# LeTalk.net
KiCad netlist of a schematic drawn in EasyEDA Pro
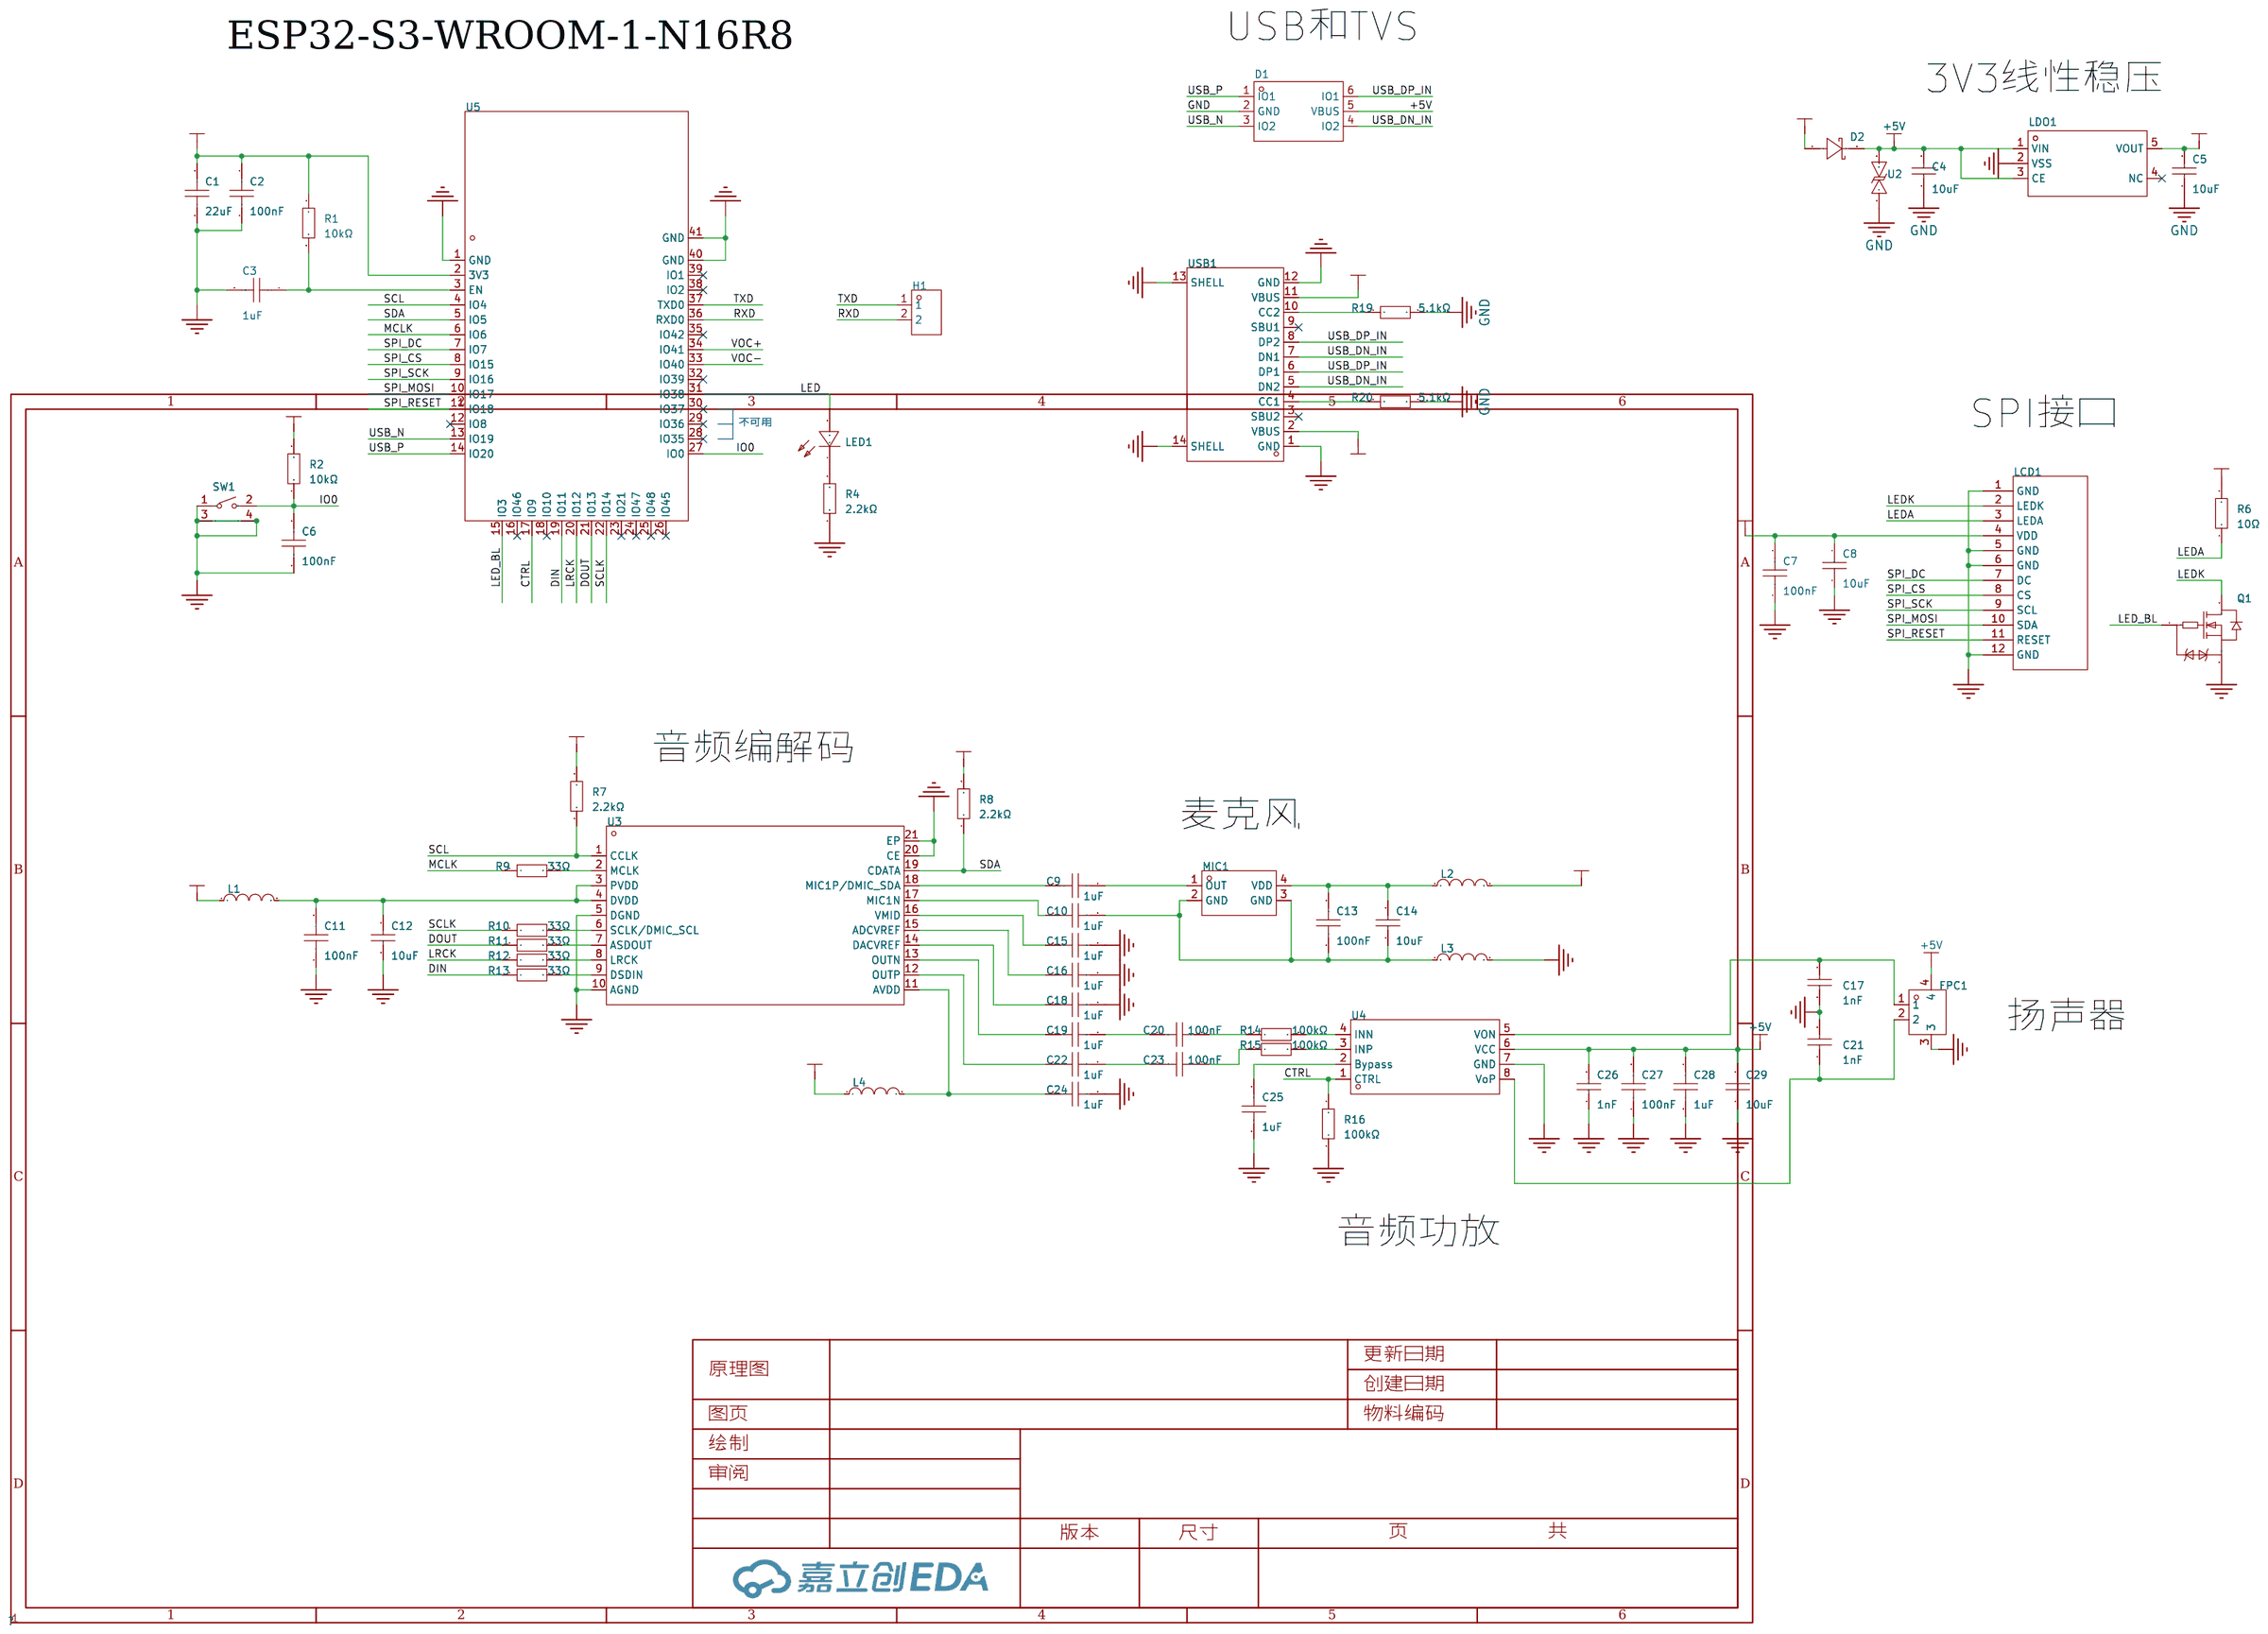
[diagram p0: schematic sheet]

(export (version "E")
  (design (tool "Eeschema 10.0.6"))
  (components
    (comp (ref "C1")
      (value "22uF")
      (footprint "easyedapro:C0603")
      (description "温度系数:X5R;精度:±20%;额定电压:10V;容值:22uF;")
      (fields
        (field (name "Manufacturer Part") "CL10A226MP8NUNE")
        (field (name "Manufacturer") "SAMSUNG(三星)")
      )
      (libsource (lib "easyedapro") (part "CL10A226MP8NUNE"))
    )
    (comp (ref "C2")
      (value "100nF")
      (footprint "easyedapro:C0402")
      (description "容值:100nF;精度:±10%;额定电压:16V;材质(温度系数):X7R;")
      (fields
        (field (name "Manufacturer Part") "CC0402KRX7R7BB104")
        (field (name "Manufacturer") "YAGEO(国巨)")
      )
      (libsource (lib "easyedapro") (part "CC0402KRX7R7BB104"))
    )
    (comp (ref "C3")
      (value "1uF")
      (footprint "easyedapro:C0402")
      (description "容值:1uF;精度:±10%;额定电压:25V;材质(温度系数):X5R;")
      (fields
        (field (name "Manufacturer Part") "CL05A105KA5NQNC")
        (field (name "Manufacturer") "SAMSUNG(三星)")
      )
      (libsource (lib "easyedapro") (part "CL05A105KA5NQNC"))
    )
    (comp (ref "C4")
      (value "10uF")
      (footprint "easyedapro:C0402")
      (description "容值:10uF;精度:±20%;额定电压:6.3V;材质(温度系数):X5R;")
      (fields
        (field (name "Manufacturer Part") "CL05A106MQ5NUNC")
        (field (name "Manufacturer") "SAMSUNG(三星)")
      )
      (libsource (lib "easyedapro") (part "CL05A106MQ5NUNC"))
    )
    (comp (ref "C5")
      (value "10uF")
      (footprint "easyedapro:C0402")
      (description "容值:10uF;精度:±20%;额定电压:6.3V;材质(温度系数):X5R;")
      (fields
        (field (name "Manufacturer Part") "CL05A106MQ5NUNC")
        (field (name "Manufacturer") "SAMSUNG(三星)")
      )
      (libsource (lib "easyedapro") (part "CL05A106MQ5NUNC"))
    )
    (comp (ref "C6")
      (value "100nF")
      (footprint "easyedapro:C0402")
      (description "容值:100nF;精度:±10%;额定电压:16V;材质(温度系数):X7R;")
      (fields
        (field (name "Manufacturer Part") "CC0402KRX7R7BB104")
        (field (name "Manufacturer") "YAGEO(国巨)")
      )
      (libsource (lib "easyedapro") (part "CC0402KRX7R7BB104"))
    )
    (comp (ref "C7")
      (value "100nF")
      (footprint "easyedapro:C0402")
      (description "容值:100nF;精度:±10%;额定电压:16V;材质(温度系数):X7R;")
      (fields
        (field (name "Manufacturer Part") "CC0402KRX7R7BB104")
        (field (name "Manufacturer") "YAGEO(国巨)")
      )
      (libsource (lib "easyedapro") (part "CC0402KRX7R7BB104"))
    )
    (comp (ref "C8")
      (value "10uF")
      (footprint "easyedapro:C0402")
      (description "容值:10uF;精度:±20%;额定电压:6.3V;材质(温度系数):X5R;")
      (fields
        (field (name "Manufacturer Part") "CL05A106MQ5NUNC")
        (field (name "Manufacturer") "SAMSUNG(三星)")
      )
      (libsource (lib "easyedapro") (part "CL05A106MQ5NUNC"))
    )
    (comp (ref "C9")
      (value "1uF")
      (footprint "easyedapro:C0402")
      (description "容值:1uF;精度:±10%;额定电压:25V;材质(温度系数):X5R;")
      (fields
        (field (name "Manufacturer Part") "CL05A105KA5NQNC")
        (field (name "Manufacturer") "SAMSUNG(三星)")
      )
      (libsource (lib "easyedapro") (part "CL05A105KA5NQNC"))
    )
    (comp (ref "C10")
      (value "1uF")
      (footprint "easyedapro:C0402")
      (description "容值:1uF;精度:±10%;额定电压:25V;材质(温度系数):X5R;")
      (fields
        (field (name "Manufacturer Part") "CL05A105KA5NQNC")
        (field (name "Manufacturer") "SAMSUNG(三星)")
      )
      (libsource (lib "easyedapro") (part "CL05A105KA5NQNC"))
    )
    (comp (ref "C11")
      (value "100nF")
      (footprint "easyedapro:C0402")
      (description "容值:100nF;精度:±10%;额定电压:16V;材质(温度系数):X7R;")
      (fields
        (field (name "Manufacturer Part") "CC0402KRX7R7BB104")
        (field (name "Manufacturer") "YAGEO(国巨)")
      )
      (libsource (lib "easyedapro") (part "CC0402KRX7R7BB104"))
    )
    (comp (ref "C12")
      (value "10uF")
      (footprint "easyedapro:C0402")
      (description "容值:10uF;精度:±20%;额定电压:6.3V;材质(温度系数):X5R;")
      (fields
        (field (name "Manufacturer Part") "CL05A106MQ5NUNC")
        (field (name "Manufacturer") "SAMSUNG(三星)")
      )
      (libsource (lib "easyedapro") (part "CL05A106MQ5NUNC"))
    )
    (comp (ref "C13")
      (value "100nF")
      (footprint "easyedapro:C0402")
      (description "容值:100nF;精度:±10%;额定电压:16V;材质(温度系数):X7R;")
      (fields
        (field (name "Manufacturer Part") "CC0402KRX7R7BB104")
        (field (name "Manufacturer") "YAGEO(国巨)")
      )
      (libsource (lib "easyedapro") (part "CC0402KRX7R7BB104"))
    )
    (comp (ref "C14")
      (value "10uF")
      (footprint "easyedapro:C0402")
      (description "容值:10uF;精度:±20%;额定电压:6.3V;材质(温度系数):X5R;")
      (fields
        (field (name "Manufacturer Part") "CL05A106MQ5NUNC")
        (field (name "Manufacturer") "SAMSUNG(三星)")
      )
      (libsource (lib "easyedapro") (part "CL05A106MQ5NUNC"))
    )
    (comp (ref "C15")
      (value "1uF")
      (footprint "easyedapro:C0402")
      (description "容值:1uF;精度:±10%;额定电压:25V;材质(温度系数):X5R;")
      (fields
        (field (name "Manufacturer Part") "CL05A105KA5NQNC")
        (field (name "Manufacturer") "SAMSUNG(三星)")
      )
      (libsource (lib "easyedapro") (part "CL05A105KA5NQNC"))
    )
    (comp (ref "C16")
      (value "1uF")
      (footprint "easyedapro:C0402")
      (description "容值:1uF;精度:±10%;额定电压:25V;材质(温度系数):X5R;")
      (fields
        (field (name "Manufacturer Part") "CL05A105KA5NQNC")
        (field (name "Manufacturer") "SAMSUNG(三星)")
      )
      (libsource (lib "easyedapro") (part "CL05A105KA5NQNC"))
    )
    (comp (ref "C17")
      (value "1nF")
      (footprint "easyedapro:C0402")
      (description "容值:1nF;精度:±10%;额定电压:50V;材质(温度系数):X7R;")
      (fields
        (field (name "Manufacturer Part") "CC0402KRX7R9BB102")
        (field (name "Manufacturer") "YAGEO(国巨)")
      )
      (libsource (lib "easyedapro") (part "0402B102K500NT"))
    )
    (comp (ref "C18")
      (value "1uF")
      (footprint "easyedapro:C0402")
      (description "容值:1uF;精度:±10%;额定电压:25V;材质(温度系数):X5R;")
      (fields
        (field (name "Manufacturer Part") "CL05A105KA5NQNC")
        (field (name "Manufacturer") "SAMSUNG(三星)")
      )
      (libsource (lib "easyedapro") (part "CL05A105KA5NQNC"))
    )
    (comp (ref "C19")
      (value "1uF")
      (footprint "easyedapro:C0402")
      (description "容值:1uF;精度:±10%;额定电压:25V;材质(温度系数):X5R;")
      (fields
        (field (name "Manufacturer Part") "CL05A105KA5NQNC")
        (field (name "Manufacturer") "SAMSUNG(三星)")
      )
      (libsource (lib "easyedapro") (part "CL05A105KA5NQNC"))
    )
    (comp (ref "C20")
      (value "100nF")
      (footprint "easyedapro:C0402")
      (description "容值:100nF;精度:±10%;额定电压:16V;材质(温度系数):X7R;")
      (fields
        (field (name "Manufacturer Part") "CC0402KRX7R7BB104")
        (field (name "Manufacturer") "YAGEO(国巨)")
      )
      (libsource (lib "easyedapro") (part "CC0402KRX7R7BB104"))
    )
    (comp (ref "C21")
      (value "1nF")
      (footprint "easyedapro:C0402")
      (description "容值:1nF;精度:±10%;额定电压:50V;材质(温度系数):X7R;")
      (fields
        (field (name "Manufacturer Part") "CC0402KRX7R9BB102")
        (field (name "Manufacturer") "YAGEO(国巨)")
      )
      (libsource (lib "easyedapro") (part "0402B102K500NT"))
    )
    (comp (ref "C22")
      (value "1uF")
      (footprint "easyedapro:C0402")
      (description "容值:1uF;精度:±10%;额定电压:25V;材质(温度系数):X5R;")
      (fields
        (field (name "Manufacturer Part") "CL05A105KA5NQNC")
        (field (name "Manufacturer") "SAMSUNG(三星)")
      )
      (libsource (lib "easyedapro") (part "CL05A105KA5NQNC"))
    )
    (comp (ref "C23")
      (value "100nF")
      (footprint "easyedapro:C0402")
      (description "容值:100nF;精度:±10%;额定电压:16V;材质(温度系数):X7R;")
      (fields
        (field (name "Manufacturer Part") "CC0402KRX7R7BB104")
        (field (name "Manufacturer") "YAGEO(国巨)")
      )
      (libsource (lib "easyedapro") (part "CC0402KRX7R7BB104"))
    )
    (comp (ref "C24")
      (value "1uF")
      (footprint "easyedapro:C0402")
      (description "容值:1uF;精度:±10%;额定电压:25V;材质(温度系数):X5R;")
      (fields
        (field (name "Manufacturer Part") "CL05A105KA5NQNC")
        (field (name "Manufacturer") "SAMSUNG(三星)")
      )
      (libsource (lib "easyedapro") (part "CL05A105KA5NQNC"))
    )
    (comp (ref "C25")
      (value "1uF")
      (footprint "easyedapro:C0402")
      (description "容值:1uF;精度:±10%;额定电压:25V;材质(温度系数):X5R;")
      (fields
        (field (name "Manufacturer Part") "CL05A105KA5NQNC")
        (field (name "Manufacturer") "SAMSUNG(三星)")
      )
      (libsource (lib "easyedapro") (part "CL05A105KA5NQNC"))
    )
    (comp (ref "C26")
      (value "1nF")
      (footprint "easyedapro:C0402")
      (description "容值:1nF;精度:±10%;额定电压:50V;材质(温度系数):X7R;")
      (fields
        (field (name "Manufacturer Part") "CC0402KRX7R9BB102")
        (field (name "Manufacturer") "YAGEO(国巨)")
      )
      (libsource (lib "easyedapro") (part "0402B102K500NT"))
    )
    (comp (ref "C27")
      (value "100nF")
      (footprint "easyedapro:C0402")
      (description "容值:100nF;精度:±10%;额定电压:16V;材质(温度系数):X7R;")
      (fields
        (field (name "Manufacturer Part") "CC0402KRX7R7BB104")
        (field (name "Manufacturer") "YAGEO(国巨)")
      )
      (libsource (lib "easyedapro") (part "CC0402KRX7R7BB104"))
    )
    (comp (ref "C28")
      (value "1uF")
      (footprint "easyedapro:C0402")
      (description "容值:1uF;精度:±10%;额定电压:25V;材质(温度系数):X5R;")
      (fields
        (field (name "Manufacturer Part") "CL05A105KA5NQNC")
        (field (name "Manufacturer") "SAMSUNG(三星)")
      )
      (libsource (lib "easyedapro") (part "CL05A105KA5NQNC"))
    )
    (comp (ref "C29")
      (value "10uF")
      (footprint "easyedapro:C0402")
      (description "容值:10uF;精度:±20%;额定电压:6.3V;材质(温度系数):X5R;")
      (fields
        (field (name "Manufacturer Part") "CL05A106MQ5NUNC")
        (field (name "Manufacturer") "SAMSUNG(三星)")
      )
      (libsource (lib "easyedapro") (part "CL05A106MQ5NUNC"))
    )
    (comp (ref "D1")
      (value "~")
      (footprint "easyedapro:SOT-23-6_L2.9-W1.6-P0.95-LS2.8-BL")
      (description "极性:-;反向关断电压（典型值）:-;击穿电压（最小值）:-;箝位电压:-;峰值脉冲电流（10/1000us）:-;")
      (fields
        (field (name "Manufacturer Part") "USBLC6-2SC6")
        (field (name "Manufacturer") "TECH PUBLIC(台舟)")
      )
      (libsource (lib "easyedapro") (part "USBLC6-2SC6_C2827654"))
    )
    (comp (ref "D2")
      (value "B5819W")
      (footprint "easyedapro:SOD-123_L2.8-W1.8-LS3.7-FD-1")
      (description "二极管配置:-;正向压降(Vf):900mV@3A;直流反向耐压(Vr):40V;整流电流:1A;")
      (fields (field (name "Manufacturer") "FUXINSEMI(富芯森美)"))
      (libsource (lib "easyedapro") (part "B5819W_C908224"))
    )
    (comp (ref "FPC1")
      (value "WAFER-MX1.25-2PWB")
      (footprint "easyedapro:CONN-SMD_2P-P1.25_XUNPU_WAFER-MX1.25-2PWB")
      (description "插针结构:1x2P;间距:1.25mm;安装方式:卧贴;总PIN数:2P;排数:1;每排PIN数:2;额定电流:1A;工作温度范围:-25°C~+85°C;")
      (fields (field (name "Manufacturer") "XUNPU(讯普)"))
      (libsource (lib "easyedapro") (part "WAFER-MX1.25-2PWB"))
    )
    (comp (ref "H1")
      (value "PZ254V-11-02P")
      (footprint "easyedapro:HDR-TH_2P-P2.54-V-M")
      (fields (field (name "Manufacturer") "XFCN(兴飞)"))
      (libsource (lib "easyedapro") (part "PZ254V-11-02P"))
    )
    (comp (ref "L1")
      (value "BLM15PX121SN1D")
      (footprint "easyedapro:L0402")
      (description "标称阻抗@测试频率:120Ω@100MHz;误差:±25%;直流电阻(DCR):55mΩ;")
      (fields (field (name "Manufacturer") "muRata(村田)"))
      (libsource (lib "easyedapro") (part "BLM15PX121SN1D"))
    )
    (comp (ref "L2")
      (value "BLM15PX121SN1D")
      (footprint "easyedapro:L0402")
      (description "标称阻抗@测试频率:120Ω@100MHz;误差:±25%;直流电阻(DCR):55mΩ;")
      (fields (field (name "Manufacturer") "muRata(村田)"))
      (libsource (lib "easyedapro") (part "BLM15PX121SN1D"))
    )
    (comp (ref "L3")
      (value "BLM15PX121SN1D")
      (footprint "easyedapro:L0402")
      (description "标称阻抗@测试频率:120Ω@100MHz;误差:±25%;直流电阻(DCR):55mΩ;")
      (fields (field (name "Manufacturer") "muRata(村田)"))
      (libsource (lib "easyedapro") (part "BLM15PX121SN1D"))
    )
    (comp (ref "L4")
      (value "BLM15PX121SN1D")
      (footprint "easyedapro:L0402")
      (description "标称阻抗@测试频率:120Ω@100MHz;误差:±25%;直流电阻(DCR):55mΩ;")
      (fields (field (name "Manufacturer") "muRata(村田)"))
      (libsource (lib "easyedapro") (part "BLM15PX121SN1D"))
    )
    (comp (ref "LCD1")
      (value "~")
      (footprint "easyedapro:YDP128H005-V3")
      (description "1.28\"/GC9A01/240x240")
      (libsource (lib "easyedapro") (part "YDP128H005-V3"))
    )
    (comp (ref "LDO1")
      (value "ME6211C33M5G-N")
      (footprint "easyedapro:SOT-23-5_L3.0-W1.7-P0.95-LS2.8-BL")
      (description "输出类型:固定;输出极性:正;最大输入电压:6V;输出电压:3.3V;输出电流:500mA;电源纹波抑制比(PSRR):70dB;")
      (fields (field (name "Manufacturer") "MICRONE(南京微盟)"))
      (libsource (lib "easyedapro") (part "ME6211C33M5G-N"))
    )
    (comp (ref "LED1")
      (value "TJ-S1706SW6TGLC6B-A5")
      (footprint "easyedapro:LED-SMD_L1.7-W0.6-RD")
      (description "发光颜色:蓝色;")
      (fields (field (name "Manufacturer") "TOGIALED(统佳)"))
      (libsource (lib "easyedapro") (part "TJ-S1706SW6TGLC6B-A5"))
    )
    (comp (ref "MIC1")
      (value "AP2718AT")
      (footprint "easyedapro:MIC-SMD_4P-L2.8-W1.9-P1.01-TL")
      (description "方向:全指向;信噪比:57dB;灵敏度:-42dB;阻抗:220Ω;")
      (fields (field (name "Manufacturer") "ALLPOWER(铨力)"))
      (libsource (lib "easyedapro") (part "AP2718AT"))
    )
    (comp (ref "Q1")
      (value "WNM6002-3/TR")
      (footprint "easyedapro:SOT-323-3_L2.0-W1.3-P1.30-LS2.1-BR")
      (fields (field (name "Manufacturer") "WILLSEMI(韦尔)"))
      (libsource (lib "easyedapro") (part "WNM6002-3/TR"))
    )
    (comp (ref "R1")
      (value "10kΩ")
      (footprint "easyedapro:R0402")
      (description "电阻类型:厚膜电阻;阻值:10kΩ;精度:±1%;功率:62.5mW;最大工作电压:50V;温度系数:±100ppm/°C;")
      (fields
        (field (name "Manufacturer Part") "0402WGF1002TCE")
        (field (name "Manufacturer") "UNI-ROYAL(厚声)")
      )
      (libsource (lib "easyedapro") (part "0402WGF1002TCE"))
    )
    (comp (ref "R2")
      (value "10kΩ")
      (footprint "easyedapro:R0402")
      (description "电阻类型:厚膜电阻;阻值:10kΩ;精度:±1%;功率:62.5mW;最大工作电压:50V;温度系数:±100ppm/°C;")
      (fields
        (field (name "Manufacturer Part") "0402WGF1002TCE")
        (field (name "Manufacturer") "UNI-ROYAL(厚声)")
      )
      (libsource (lib "easyedapro") (part "0402WGF1002TCE"))
    )
    (comp (ref "R4")
      (value "2.2kΩ")
      (footprint "easyedapro:R0402")
      (description "电阻类型:厚膜电阻;阻值:2.2kΩ;精度:±1%;功率:62.5mW;最大工作电压:50V;温度系数:±100ppm/°C;")
      (fields
        (field (name "Manufacturer Part") "0402WGF2201TCE")
        (field (name "Manufacturer") "UNI-ROYAL(厚声)")
      )
      (libsource (lib "easyedapro") (part "0402WGF2201TCE"))
    )
    (comp (ref "R6")
      (value "10Ω")
      (footprint "easyedapro:R0402")
      (description "电阻类型:厚膜电阻;阻值:10Ω;精度:±1%;功率:62.5mW;最大工作电压:50V;温度系数:±200ppm/°C;")
      (fields
        (field (name "Manufacturer Part") "0402WGF100JTCE")
        (field (name "Manufacturer") "UNI-ROYAL(厚声)")
      )
      (libsource (lib "easyedapro") (part "0402WGF100JTCE"))
    )
    (comp (ref "R7")
      (value "2.2kΩ")
      (footprint "easyedapro:R0402")
      (description "电阻类型:厚膜电阻;阻值:2.2kΩ;精度:±1%;功率:62.5mW;最大工作电压:50V;温度系数:±100ppm/°C;")
      (fields
        (field (name "Manufacturer Part") "0402WGF2201TCE")
        (field (name "Manufacturer") "UNI-ROYAL(厚声)")
      )
      (libsource (lib "easyedapro") (part "0402WGF2201TCE"))
    )
    (comp (ref "R8")
      (value "2.2kΩ")
      (footprint "easyedapro:R0402")
      (description "电阻类型:厚膜电阻;阻值:2.2kΩ;精度:±1%;功率:62.5mW;最大工作电压:50V;温度系数:±100ppm/°C;")
      (fields
        (field (name "Manufacturer Part") "0402WGF2201TCE")
        (field (name "Manufacturer") "UNI-ROYAL(厚声)")
      )
      (libsource (lib "easyedapro") (part "0402WGF2201TCE"))
    )
    (comp (ref "R9")
      (value "33Ω")
      (footprint "easyedapro:R0402")
      (description "电阻类型:厚膜电阻;阻值:33Ω;精度:±1%;功率:62.5mW;最大工作电压:50V;温度系数:±100ppm/°C;")
      (fields
        (field (name "Manufacturer Part") "0402WGF330JTCE")
        (field (name "Manufacturer") "UNI-ROYAL(厚声)")
      )
      (libsource (lib "easyedapro") (part "0402WGF330JTCE"))
    )
    (comp (ref "R10")
      (value "33Ω")
      (footprint "easyedapro:R0402")
      (description "电阻类型:厚膜电阻;阻值:33Ω;精度:±1%;功率:62.5mW;最大工作电压:50V;温度系数:±100ppm/°C;")
      (fields
        (field (name "Manufacturer Part") "0402WGF330JTCE")
        (field (name "Manufacturer") "UNI-ROYAL(厚声)")
      )
      (libsource (lib "easyedapro") (part "0402WGF330JTCE"))
    )
    (comp (ref "R11")
      (value "33Ω")
      (footprint "easyedapro:R0402")
      (description "电阻类型:厚膜电阻;阻值:33Ω;精度:±1%;功率:62.5mW;最大工作电压:50V;温度系数:±100ppm/°C;")
      (fields
        (field (name "Manufacturer Part") "0402WGF330JTCE")
        (field (name "Manufacturer") "UNI-ROYAL(厚声)")
      )
      (libsource (lib "easyedapro") (part "0402WGF330JTCE"))
    )
    (comp (ref "R12")
      (value "33Ω")
      (footprint "easyedapro:R0402")
      (description "电阻类型:厚膜电阻;阻值:33Ω;精度:±1%;功率:62.5mW;最大工作电压:50V;温度系数:±100ppm/°C;")
      (fields
        (field (name "Manufacturer Part") "0402WGF330JTCE")
        (field (name "Manufacturer") "UNI-ROYAL(厚声)")
      )
      (libsource (lib "easyedapro") (part "0402WGF330JTCE"))
    )
    (comp (ref "R13")
      (value "33Ω")
      (footprint "easyedapro:R0402")
      (description "电阻类型:厚膜电阻;阻值:33Ω;精度:±1%;功率:62.5mW;最大工作电压:50V;温度系数:±100ppm/°C;")
      (fields
        (field (name "Manufacturer Part") "0402WGF330JTCE")
        (field (name "Manufacturer") "UNI-ROYAL(厚声)")
      )
      (libsource (lib "easyedapro") (part "0402WGF330JTCE"))
    )
    (comp (ref "R14")
      (value "100kΩ")
      (footprint "easyedapro:R0402")
      (description "电阻类型:厚膜电阻;阻值:100kΩ;精度:±1%;功率:62.5mW;最大工作电压:50V;温度系数:±100ppm/°C;")
      (fields (field (name "Manufacturer Part") "RC0402FR-07100KL") (field (name "Manufacturer") "YAGEO(国巨)"))
      (libsource (lib "easyedapro") (part "RC0402FR-07100KL"))
    )
    (comp (ref "R15")
      (value "100kΩ")
      (footprint "easyedapro:R0402")
      (description "电阻类型:厚膜电阻;阻值:100kΩ;精度:±1%;功率:62.5mW;最大工作电压:50V;温度系数:±100ppm/°C;")
      (fields (field (name "Manufacturer Part") "RC0402FR-07100KL") (field (name "Manufacturer") "YAGEO(国巨)"))
      (libsource (lib "easyedapro") (part "RC0402FR-07100KL"))
    )
    (comp (ref "R16")
      (value "100kΩ")
      (footprint "easyedapro:R0402")
      (description "电阻类型:厚膜电阻;阻值:100kΩ;精度:±1%;功率:62.5mW;最大工作电压:50V;温度系数:±100ppm/°C;")
      (fields (field (name "Manufacturer Part") "RC0402FR-07100KL") (field (name "Manufacturer") "YAGEO(国巨)"))
      (libsource (lib "easyedapro") (part "RC0402FR-07100KL"))
    )
    (comp (ref "R19")
      (value "5.1kΩ")
      (footprint "easyedapro:R0402")
      (description "阻值:5.1kΩ;精度:±1%;功率:62.5mW;")
      (fields (field (name "Manufacturer Part") "RMC04025.1K1%N") (field (name "Manufacturer") "Tyohm(幸亚电阻)"))
      (libsource (lib "easyedapro") (part "RMC04025.1K1%N"))
    )
    (comp (ref "R20")
      (value "5.1kΩ")
      (footprint "easyedapro:R0402")
      (description "阻值:5.1kΩ;精度:±1%;功率:62.5mW;")
      (fields (field (name "Manufacturer Part") "RMC04025.1K1%N") (field (name "Manufacturer") "Tyohm(幸亚电阻)"))
      (libsource (lib "easyedapro") (part "RMC04025.1K1%N"))
    )
    (comp (ref "SW1")
      (value "GT-TC191A-H026-L60")
      (footprint "easyedapro:KEY-SMD_GT-TC191A-H026-L60")
      (fields (field (name "Manufacturer") "G-Switch(品赞)"))
      (libsource (lib "easyedapro") (part "GT-TC191A-H026-L60"))
    )
    (comp (ref "U2")
      (value "SYT01N05DWC")
      (footprint "easyedapro:DFN-2L_L1.0-W0.6-P0.65-BI-2")
      (fields (field (name "Manufacturer") "silergy(矽力杰)"))
      (libsource (lib "easyedapro") (part "SYT01N05DWC"))
    )
    (comp (ref "U3")
      (value "ES8311")
      (footprint "easyedapro:WQFN-20_L3.0-W3.0-P0.40-BL-EP1.7")
      (fields (field (name "Manufacturer") "Everest-semi(顺芯)"))
      (libsource (lib "easyedapro") (part "ES8311"))
    )
    (comp (ref "U4")
      (value "NS4150B")
      (footprint "easyedapro:MSOP-8_L3.0-W3.0-P0.65-LS5.0-BL")
      (description "功放类型:D类功放;输出功率:3Wx1@4Ω;")
      (fields (field (name "Manufacturer") "Nsiway(纳芯威)"))
      (libsource (lib "easyedapro") (part "NS4150"))
    )
    (comp (ref "U5")
      (value "ESP32-S3-WROOM-1-N16R8")
      (footprint "easyedapro:WIRELM-SMD_ESP32-S3-WROOM-1")
      (fields (field (name "Manufacturer") "ESPRESSIF(乐鑫)"))
      (libsource (lib "easyedapro") (part "ESP32-S3-WROOM-1(N16R8)"))
    )
    (comp (ref "USB1")
      (value "TYPE-C 16PIN 2MD(073)")
      (footprint "easyedapro:USB-C-SMD_TYPE-C-6PIN-2MD-073")
      (description "连接器类型:Type-C;标准:USB 3.1;公母:母;安装方式:卧贴;触点数量:16P;端口数量:1;额定电流 - 电源:5A;工作温度范围:-25°C~+85°C;")
      (fields (field (name "Manufacturer") "SHOU HAN(首韩)"))
      (libsource (lib "easyedapro") (part "TYPE-C 16PIN 2MD(073)"))
    )
  )
  (nets
    (net (code "1") (name "+3V3") (class "Default")
      (node (ref "C1") (pin "2") (pinfunction "2_2") (pintype "input"))
      (node (ref "C2") (pin "2") (pinfunction "2_2") (pintype "unspecified"))
      (node (ref "C5") (pin "2") (pinfunction "2_2") (pintype "input"))
      (node (ref "C7") (pin "2") (pinfunction "2_2") (pintype "unspecified"))
      (node (ref "C8") (pin "2") (pinfunction "2_2") (pintype "input"))
      (node (ref "L1") (pin "1") (pinfunction "1_1") (pintype "unspecified"))
      (node (ref "L2") (pin "2") (pinfunction "2_2") (pintype "unspecified"))
      (node (ref "L4") (pin "1") (pinfunction "1_1") (pintype "unspecified"))
      (node (ref "LCD1") (pin "4") (pinfunction "VDD_4") (pintype "unspecified"))
      (node (ref "LDO1") (pin "5") (pinfunction "VOUT_5") (pintype "input"))
      (node (ref "R1") (pin "1") (pinfunction "1_1") (pintype "input"))
      (node (ref "R2") (pin "2") (pinfunction "2_2") (pintype "input"))
      (node (ref "R6") (pin "2") (pinfunction "2_2") (pintype "input"))
      (node (ref "R7") (pin "2") (pinfunction "2_2") (pintype "input"))
      (node (ref "R8") (pin "2") (pinfunction "2_2") (pintype "input"))
      (node (ref "U5") (pin "2") (pinfunction "3V3_2") (pintype "unspecified"))
    )
    (net (code "2") (name "+5V") (class "Default")
      (node (ref "C26") (pin "2") (pinfunction "2_2") (pintype "input"))
      (node (ref "C27") (pin "2") (pinfunction "2_2") (pintype "unspecified"))
      (node (ref "C28") (pin "1") (pinfunction "1_1") (pintype "unspecified"))
      (node (ref "C29") (pin "2") (pinfunction "2_2") (pintype "input"))
      (node (ref "C4") (pin "2") (pinfunction "2_2") (pintype "input"))
      (node (ref "D1") (pin "5") (pinfunction "VBUS_5") (pintype "input"))
      (node (ref "D2") (pin "2") (pinfunction "K_2") (pintype "unspecified"))
      (node (ref "FPC1") (pin "4") (pinfunction "4_4") (pintype "unspecified"))
      (node (ref "LDO1") (pin "1") (pinfunction "VIN_1") (pintype "input"))
      (node (ref "LDO1") (pin "3") (pinfunction "CE_3") (pintype "input"))
      (node (ref "U2") (pin "2") (pinfunction "2_2") (pintype "input"))
      (node (ref "U4") (pin "6") (pinfunction "VCC_6") (pintype "unspecified"))
    )
    (net (code "3") (name "/CTRL") (class "Default")
      (node (ref "R16") (pin "2") (pinfunction "2_2") (pintype "input"))
      (node (ref "U4") (pin "1") (pinfunction "CTRL_1") (pintype "unspecified"))
      (node (ref "U5") (pin "17") (pinfunction "IO9_17") (pintype "unspecified"))
    )
    (net (code "4") (name "/DIN") (class "Default")
      (node (ref "R13") (pin "1") (pinfunction "1_1") (pintype "input"))
      (node (ref "U5") (pin "19") (pinfunction "IO11_19") (pintype "unspecified"))
    )
    (net (code "5") (name "/DOUT") (class "Default")
      (node (ref "R11") (pin "1") (pinfunction "1_1") (pintype "input"))
      (node (ref "U5") (pin "21") (pinfunction "IO13_21") (pintype "unspecified"))
    )
    (net (code "6") (name "/IO0") (class "Default")
      (node (ref "C6") (pin "2") (pinfunction "2_2") (pintype "unspecified"))
      (node (ref "R2") (pin "1") (pinfunction "1_1") (pintype "input"))
      (node (ref "SW1") (pin "2") (pinfunction "2_2") (pintype "unspecified"))
      (node (ref "U5") (pin "27") (pinfunction "IO0_27") (pintype "unspecified"))
    )
    (net (code "7") (name "/LED") (class "Default")
      (node (ref "LED1") (pin "2") (pinfunction "2_2") (pintype "unspecified"))
      (node (ref "U5") (pin "31") (pinfunction "IO38_31") (pintype "unspecified"))
    )
    (net (code "8") (name "/LEDA") (class "Default")
      (node (ref "LCD1") (pin "3") (pinfunction "LEDA_3") (pintype "input"))
      (node (ref "R6") (pin "1") (pinfunction "1_1") (pintype "input"))
    )
    (net (code "9") (name "/LEDK") (class "Default")
      (node (ref "LCD1") (pin "2") (pinfunction "LEDK_2") (pintype "input"))
      (node (ref "Q1") (pin "3") (pinfunction "D_3") (pintype "unspecified"))
    )
    (net (code "10") (name "/LED_BL") (class "Default")
      (node (ref "Q1") (pin "1") (pinfunction "G_1") (pintype "unspecified"))
      (node (ref "U5") (pin "15") (pinfunction "IO3_15") (pintype "unspecified"))
    )
    (net (code "11") (name "/LRCK") (class "Default")
      (node (ref "R12") (pin "1") (pinfunction "1_1") (pintype "input"))
      (node (ref "U5") (pin "20") (pinfunction "IO12_20") (pintype "unspecified"))
    )
    (net (code "12") (name "/MCLK") (class "Default")
      (node (ref "R9") (pin "1") (pinfunction "1_1") (pintype "input"))
      (node (ref "U5") (pin "6") (pinfunction "IO6_6") (pintype "unspecified"))
    )
    (net (code "13") (name "/RXD") (class "Default")
      (node (ref "H1") (pin "2") (pinfunction "2_2") (pintype "unspecified"))
      (node (ref "U5") (pin "36") (pinfunction "RXD0_36") (pintype "unspecified"))
    )
    (net (code "14") (name "/SCL") (class "Default")
      (node (ref "R7") (pin "1") (pinfunction "1_1") (pintype "input"))
      (node (ref "U3") (pin "1") (pinfunction "CCLK_1") (pintype "unspecified"))
      (node (ref "U5") (pin "4") (pinfunction "IO4_4") (pintype "unspecified"))
    )
    (net (code "15") (name "/SCLK") (class "Default")
      (node (ref "R10") (pin "1") (pinfunction "1_1") (pintype "input"))
      (node (ref "U5") (pin "22") (pinfunction "IO14_22") (pintype "unspecified"))
    )
    (net (code "16") (name "/SDA") (class "Default")
      (node (ref "R8") (pin "1") (pinfunction "1_1") (pintype "input"))
      (node (ref "U3") (pin "19") (pinfunction "CDATA_19") (pintype "unspecified"))
      (node (ref "U5") (pin "5") (pinfunction "IO5_5") (pintype "unspecified"))
    )
    (net (code "17") (name "/SPI_CS") (class "Default")
      (node (ref "LCD1") (pin "8") (pinfunction "CS_8") (pintype "input"))
      (node (ref "U5") (pin "8") (pinfunction "IO15_8") (pintype "unspecified"))
    )
    (net (code "18") (name "/SPI_DC") (class "Default")
      (node (ref "LCD1") (pin "7") (pinfunction "DC_7") (pintype "input"))
      (node (ref "U5") (pin "7") (pinfunction "IO7_7") (pintype "unspecified"))
    )
    (net (code "19") (name "/SPI_MOSI") (class "Default")
      (node (ref "LCD1") (pin "10") (pinfunction "SDA_10") (pintype "input"))
      (node (ref "U5") (pin "10") (pinfunction "IO17_10") (pintype "unspecified"))
    )
    (net (code "20") (name "/SPI_RESET") (class "Default")
      (node (ref "LCD1") (pin "11") (pinfunction "RESET_11") (pintype "input"))
      (node (ref "U5") (pin "11") (pinfunction "IO18_11") (pintype "unspecified"))
    )
    (net (code "21") (name "/SPI_SCK") (class "Default")
      (node (ref "LCD1") (pin "9") (pinfunction "SCL_9") (pintype "input"))
      (node (ref "U5") (pin "9") (pinfunction "IO16_9") (pintype "unspecified"))
    )
    (net (code "22") (name "/TXD") (class "Default")
      (node (ref "H1") (pin "1") (pinfunction "1_1") (pintype "unspecified"))
      (node (ref "U5") (pin "37") (pinfunction "TXD0_37") (pintype "unspecified"))
    )
    (net (code "23") (name "/USB_DN_IN") (class "Default")
      (node (ref "D1") (pin "4") (pinfunction "IO2_4") (pintype "input"))
      (node (ref "USB1") (pin "5") (pinfunction "DN2_5") (pintype "unspecified"))
      (node (ref "USB1") (pin "7") (pinfunction "DN1_7") (pintype "unspecified"))
    )
    (net (code "24") (name "/USB_DP_IN") (class "Default")
      (node (ref "D1") (pin "6") (pinfunction "IO1_6") (pintype "input"))
      (node (ref "USB1") (pin "6") (pinfunction "DP1_6") (pintype "unspecified"))
      (node (ref "USB1") (pin "8") (pinfunction "DP2_8") (pintype "unspecified"))
    )
    (net (code "25") (name "/USB_N") (class "Default")
      (node (ref "D1") (pin "3") (pinfunction "IO2_3") (pintype "input"))
      (node (ref "U5") (pin "13") (pinfunction "IO19_13") (pintype "unspecified"))
    )
    (net (code "26") (name "/USB_P") (class "Default")
      (node (ref "D1") (pin "1") (pinfunction "IO1_1") (pintype "input"))
      (node (ref "U5") (pin "14") (pinfunction "IO20_14") (pintype "unspecified"))
    )
    (net (code "27") (name "/VOC+") (class "Default")
      (node (ref "U5") (pin "34") (pinfunction "IO41_34") (pintype "unspecified"))
    )
    (net (code "28") (name "/VOC-") (class "Default")
      (node (ref "U5") (pin "33") (pinfunction "IO40_33") (pintype "unspecified"))
    )
    (net (code "29") (name "GND") (class "Default")
      (node (ref "C1") (pin "1") (pinfunction "1_1") (pintype "input"))
      (node (ref "C11") (pin "1") (pinfunction "1_1") (pintype "unspecified"))
      (node (ref "C12") (pin "1") (pinfunction "1_1") (pintype "input"))
      (node (ref "C15") (pin "2") (pinfunction "2_2") (pintype "unspecified"))
      (node (ref "C16") (pin "2") (pinfunction "2_2") (pintype "unspecified"))
      (node (ref "C17") (pin "1") (pinfunction "1_1") (pintype "input"))
      (node (ref "C18") (pin "2") (pinfunction "2_2") (pintype "unspecified"))
      (node (ref "C2") (pin "1") (pinfunction "1_1") (pintype "unspecified"))
      (node (ref "C21") (pin "2") (pinfunction "2_2") (pintype "input"))
      (node (ref "C24") (pin "2") (pinfunction "2_2") (pintype "unspecified"))
      (node (ref "C25") (pin "2") (pinfunction "2_2") (pintype "unspecified"))
      (node (ref "C26") (pin "1") (pinfunction "1_1") (pintype "input"))
      (node (ref "C27") (pin "1") (pinfunction "1_1") (pintype "unspecified"))
      (node (ref "C28") (pin "2") (pinfunction "2_2") (pintype "unspecified"))
      (node (ref "C29") (pin "1") (pinfunction "1_1") (pintype "input"))
      (node (ref "C3") (pin "2") (pinfunction "2_2") (pintype "unspecified"))
      (node (ref "C4") (pin "1") (pinfunction "1_1") (pintype "input"))
      (node (ref "C5") (pin "1") (pinfunction "1_1") (pintype "input"))
      (node (ref "C6") (pin "1") (pinfunction "1_1") (pintype "unspecified"))
      (node (ref "C7") (pin "1") (pinfunction "1_1") (pintype "unspecified"))
      (node (ref "C8") (pin "1") (pinfunction "1_1") (pintype "input"))
      (node (ref "D1") (pin "2") (pinfunction "GND_2") (pintype "input"))
      (node (ref "FPC1") (pin "3") (pinfunction "3_3") (pintype "unspecified"))
      (node (ref "L3") (pin "2") (pinfunction "2_2") (pintype "unspecified"))
      (node (ref "LCD1") (pin "1") (pinfunction "GND_1") (pintype "unspecified"))
      (node (ref "LCD1") (pin "12") (pinfunction "GND_12") (pintype "unspecified"))
      (node (ref "LCD1") (pin "5") (pinfunction "GND_5") (pintype "unspecified"))
      (node (ref "LCD1") (pin "6") (pinfunction "GND_6") (pintype "unspecified"))
      (node (ref "LDO1") (pin "2") (pinfunction "VSS_2") (pintype "input"))
      (node (ref "Q1") (pin "2") (pinfunction "S_2") (pintype "unspecified"))
      (node (ref "R16") (pin "1") (pinfunction "1_1") (pintype "input"))
      (node (ref "R19") (pin "2") (pinfunction "2_2") (pintype "input"))
      (node (ref "R20") (pin "2") (pinfunction "2_2") (pintype "input"))
      (node (ref "R4") (pin "2") (pinfunction "2_2") (pintype "input"))
      (node (ref "SW1") (pin "1") (pinfunction "1_1") (pintype "unspecified"))
      (node (ref "SW1") (pin "3") (pinfunction "3_3") (pintype "unspecified"))
      (node (ref "SW1") (pin "4") (pinfunction "4_4") (pintype "unspecified"))
      (node (ref "U2") (pin "1") (pinfunction "1_1") (pintype "input"))
      (node (ref "U3") (pin "10") (pinfunction "AGND_10") (pintype "unspecified"))
      (node (ref "U3") (pin "20") (pinfunction "CE_20") (pintype "unspecified"))
      (node (ref "U3") (pin "21") (pinfunction "EP_21") (pintype "unspecified"))
      (node (ref "U3") (pin "5") (pinfunction "DGND_5") (pintype "unspecified"))
      (node (ref "U4") (pin "7") (pinfunction "GND_7") (pintype "unspecified"))
      (node (ref "U5") (pin "1") (pinfunction "GND_1") (pintype "unspecified"))
      (node (ref "U5") (pin "40") (pinfunction "GND_40") (pintype "unspecified"))
      (node (ref "U5") (pin "41") (pinfunction "GND_41") (pintype "unspecified"))
      (node (ref "USB1") (pin "1") (pinfunction "GND_1") (pintype "unspecified"))
      (node (ref "USB1") (pin "12") (pinfunction "GND_12") (pintype "unspecified"))
      (node (ref "USB1") (pin "13") (pinfunction "SHELL_13") (pintype "unspecified"))
      (node (ref "USB1") (pin "14") (pinfunction "SHELL_14") (pintype "unspecified"))
    )
    (net (code "30") (name "Net-(C10-Pad2)") (class "Default")
      (node (ref "C10") (pin "2") (pinfunction "2_2") (pintype "unspecified"))
      (node (ref "C13") (pin "1") (pinfunction "1_1") (pintype "unspecified"))
      (node (ref "C14") (pin "1") (pinfunction "1_1") (pintype "input"))
      (node (ref "L3") (pin "1") (pinfunction "1_1") (pintype "unspecified"))
      (node (ref "MIC1") (pin "2") (pinfunction "GND_2") (pintype "unspecified"))
      (node (ref "MIC1") (pin "3") (pinfunction "GND_3") (pintype "unspecified"))
    )
    (net (code "31") (name "Net-(C19-Pad2)") (class "Default")
      (node (ref "C19") (pin "2") (pinfunction "2_2") (pintype "unspecified"))
      (node (ref "C20") (pin "2") (pinfunction "2_2") (pintype "unspecified"))
    )
    (net (code "32") (name "Net-(C20-Pad1)") (class "Default")
      (node (ref "C20") (pin "1") (pinfunction "1_1") (pintype "unspecified"))
      (node (ref "R14") (pin "1") (pinfunction "1_1") (pintype "input"))
    )
    (net (code "33") (name "Net-(C22-Pad2)") (class "Default")
      (node (ref "C22") (pin "2") (pinfunction "2_2") (pintype "unspecified"))
      (node (ref "C23") (pin "2") (pinfunction "2_2") (pintype "unspecified"))
    )
    (net (code "34") (name "Net-(C23-Pad1)") (class "Default")
      (node (ref "C23") (pin "1") (pinfunction "1_1") (pintype "unspecified"))
      (node (ref "R15") (pin "1") (pinfunction "1_1") (pintype "input"))
    )
    (net (code "35") (name "Net-(LED1-Pad1)") (class "Default")
      (node (ref "LED1") (pin "1") (pinfunction "1_1") (pintype "unspecified"))
      (node (ref "R4") (pin "1") (pinfunction "1_1") (pintype "input"))
    )
    (net (code "36") (name "Net-(MIC1-OUT)") (class "Default")
      (node (ref "C9") (pin "2") (pinfunction "2_2") (pintype "unspecified"))
      (node (ref "MIC1") (pin "1") (pinfunction "OUT_1") (pintype "unspecified"))
    )
    (net (code "37") (name "Net-(MIC1-VDD)") (class "Default")
      (node (ref "C13") (pin "2") (pinfunction "2_2") (pintype "unspecified"))
      (node (ref "C14") (pin "2") (pinfunction "2_2") (pintype "input"))
      (node (ref "L2") (pin "1") (pinfunction "1_1") (pintype "unspecified"))
      (node (ref "MIC1") (pin "4") (pinfunction "VDD_4") (pintype "unspecified"))
    )
    (net (code "38") (name "Net-(U3-ADCVREF)") (class "Default")
      (node (ref "C16") (pin "1") (pinfunction "1_1") (pintype "unspecified"))
      (node (ref "U3") (pin "15") (pinfunction "ADCVREF_15") (pintype "unspecified"))
    )
    (net (code "39") (name "Net-(U3-ASDOUT)") (class "Default")
      (node (ref "R11") (pin "2") (pinfunction "2_2") (pintype "input"))
      (node (ref "U3") (pin "7") (pinfunction "ASDOUT_7") (pintype "unspecified"))
    )
    (net (code "40") (name "Net-(U3-AVDD)") (class "Default")
      (node (ref "C24") (pin "1") (pinfunction "1_1") (pintype "unspecified"))
      (node (ref "L4") (pin "2") (pinfunction "2_2") (pintype "unspecified"))
      (node (ref "U3") (pin "11") (pinfunction "AVDD_11") (pintype "unspecified"))
    )
    (net (code "41") (name "Net-(U3-DACVREF)") (class "Default")
      (node (ref "C18") (pin "1") (pinfunction "1_1") (pintype "unspecified"))
      (node (ref "U3") (pin "14") (pinfunction "DACVREF_14") (pintype "unspecified"))
    )
    (net (code "42") (name "Net-(U3-DSDIN)") (class "Default")
      (node (ref "R13") (pin "2") (pinfunction "2_2") (pintype "input"))
      (node (ref "U3") (pin "9") (pinfunction "DSDIN_9") (pintype "unspecified"))
    )
    (net (code "43") (name "Net-(U3-DVDD)") (class "Default")
      (node (ref "C11") (pin "2") (pinfunction "2_2") (pintype "unspecified"))
      (node (ref "C12") (pin "2") (pinfunction "2_2") (pintype "input"))
      (node (ref "L1") (pin "2") (pinfunction "2_2") (pintype "unspecified"))
      (node (ref "U3") (pin "3") (pinfunction "PVDD_3") (pintype "unspecified"))
      (node (ref "U3") (pin "4") (pinfunction "DVDD_4") (pintype "unspecified"))
    )
    (net (code "44") (name "Net-(U3-LRCK)") (class "Default")
      (node (ref "R12") (pin "2") (pinfunction "2_2") (pintype "input"))
      (node (ref "U3") (pin "8") (pinfunction "LRCK_8") (pintype "unspecified"))
    )
    (net (code "45") (name "Net-(U3-MCLK)") (class "Default")
      (node (ref "R9") (pin "2") (pinfunction "2_2") (pintype "input"))
      (node (ref "U3") (pin "2") (pinfunction "MCLK_2") (pintype "unspecified"))
    )
    (net (code "46") (name "Net-(U3-MIC1N)") (class "Default")
      (node (ref "C10") (pin "1") (pinfunction "1_1") (pintype "unspecified"))
      (node (ref "U3") (pin "17") (pinfunction "MIC1N_17") (pintype "unspecified"))
    )
    (net (code "47") (name "Net-(U3-MIC1P{slash}DMIC_SDA)") (class "Default")
      (node (ref "C9") (pin "1") (pinfunction "1_1") (pintype "unspecified"))
      (node (ref "U3") (pin "18") (pinfunction "MIC1P/DMIC_SDA_18") (pintype "unspecified"))
    )
    (net (code "48") (name "Net-(U3-OUTN)") (class "Default")
      (node (ref "C19") (pin "1") (pinfunction "1_1") (pintype "unspecified"))
      (node (ref "U3") (pin "13") (pinfunction "OUTN_13") (pintype "unspecified"))
    )
    (net (code "49") (name "Net-(U3-OUTP)") (class "Default")
      (node (ref "C22") (pin "1") (pinfunction "1_1") (pintype "unspecified"))
      (node (ref "U3") (pin "12") (pinfunction "OUTP_12") (pintype "unspecified"))
    )
    (net (code "50") (name "Net-(U3-SCLK{slash}DMIC_SCL)") (class "Default")
      (node (ref "R10") (pin "2") (pinfunction "2_2") (pintype "input"))
      (node (ref "U3") (pin "6") (pinfunction "SCLK/DMIC_SCL_6") (pintype "unspecified"))
    )
    (net (code "51") (name "Net-(U3-VMID)") (class "Default")
      (node (ref "C15") (pin "1") (pinfunction "1_1") (pintype "unspecified"))
      (node (ref "U3") (pin "16") (pinfunction "VMID_16") (pintype "unspecified"))
    )
    (net (code "52") (name "Net-(U4-Bypass)") (class "Default")
      (node (ref "C25") (pin "1") (pinfunction "1_1") (pintype "unspecified"))
      (node (ref "U4") (pin "2") (pinfunction "Bypass_2") (pintype "unspecified"))
    )
    (net (code "53") (name "Net-(U4-INN)") (class "Default")
      (node (ref "R14") (pin "2") (pinfunction "2_2") (pintype "input"))
      (node (ref "U4") (pin "4") (pinfunction "INN_4") (pintype "unspecified"))
    )
    (net (code "54") (name "Net-(U4-INP)") (class "Default")
      (node (ref "R15") (pin "2") (pinfunction "2_2") (pintype "input"))
      (node (ref "U4") (pin "3") (pinfunction "INP_3") (pintype "unspecified"))
    )
    (net (code "55") (name "Net-(U4-VON)") (class "Default")
      (node (ref "C17") (pin "2") (pinfunction "2_2") (pintype "input"))
      (node (ref "FPC1") (pin "1") (pinfunction "1_1") (pintype "unspecified"))
      (node (ref "U4") (pin "5") (pinfunction "VON_5") (pintype "unspecified"))
    )
    (net (code "56") (name "Net-(U4-VoP)") (class "Default")
      (node (ref "C21") (pin "1") (pinfunction "1_1") (pintype "input"))
      (node (ref "FPC1") (pin "2") (pinfunction "2_2") (pintype "unspecified"))
      (node (ref "U4") (pin "8") (pinfunction "VoP_8") (pintype "unspecified"))
    )
    (net (code "57") (name "Net-(U5-EN)") (class "Default")
      (node (ref "C3") (pin "1") (pinfunction "1_1") (pintype "unspecified"))
      (node (ref "R1") (pin "2") (pinfunction "2_2") (pintype "input"))
      (node (ref "U5") (pin "3") (pinfunction "EN_3") (pintype "unspecified"))
    )
    (net (code "58") (name "Net-(USB1-CC1)") (class "Default")
      (node (ref "R20") (pin "1") (pinfunction "1_1") (pintype "input"))
      (node (ref "USB1") (pin "4") (pinfunction "CC1_4") (pintype "unspecified"))
    )
    (net (code "59") (name "Net-(USB1-CC2)") (class "Default")
      (node (ref "R19") (pin "1") (pinfunction "1_1") (pintype "input"))
      (node (ref "USB1") (pin "10") (pinfunction "CC2_10") (pintype "unspecified"))
    )
    (net (code "60") (name "VBUS") (class "Default")
      (node (ref "D2") (pin "1") (pinfunction "A_1") (pintype "unspecified"))
      (node (ref "USB1") (pin "11") (pinfunction "VBUS_11") (pintype "unspecified"))
      (node (ref "USB1") (pin "2") (pinfunction "VBUS_2") (pintype "unspecified"))
    )
    (net (code "61") (name "unconnected-(LDO1-NC-Pad4)") (class "Default")
      (node (ref "LDO1") (pin "4") (pinfunction "NC_4") (pintype "input+no_connect"))
    )
    (net (code "62") (name "unconnected-(U5-IO1-Pad39)") (class "Default")
      (node (ref "U5") (pin "39") (pinfunction "IO1_39") (pintype "unspecified+no_connect"))
    )
    (net (code "63") (name "unconnected-(U5-IO2-Pad38)") (class "Default")
      (node (ref "U5") (pin "38") (pinfunction "IO2_38") (pintype "unspecified+no_connect"))
    )
    (net (code "64") (name "unconnected-(U5-IO8-Pad12)") (class "Default")
      (node (ref "U5") (pin "12") (pinfunction "IO8_12") (pintype "unspecified+no_connect"))
    )
    (net (code "65") (name "unconnected-(U5-IO10-Pad18)") (class "Default")
      (node (ref "U5") (pin "18") (pinfunction "IO10_18") (pintype "unspecified+no_connect"))
    )
    (net (code "66") (name "unconnected-(U5-IO21-Pad23)") (class "Default")
      (node (ref "U5") (pin "23") (pinfunction "IO21_23") (pintype "unspecified+no_connect"))
    )
    (net (code "67") (name "unconnected-(U5-IO35-Pad28)") (class "Default")
      (node (ref "U5") (pin "28") (pinfunction "IO35_28") (pintype "unspecified+no_connect"))
    )
    (net (code "68") (name "unconnected-(U5-IO36-Pad29)") (class "Default")
      (node (ref "U5") (pin "29") (pinfunction "IO36_29") (pintype "unspecified+no_connect"))
    )
    (net (code "69") (name "unconnected-(U5-IO37-Pad30)") (class "Default")
      (node (ref "U5") (pin "30") (pinfunction "IO37_30") (pintype "unspecified+no_connect"))
    )
    (net (code "70") (name "unconnected-(U5-IO39-Pad32)") (class "Default")
      (node (ref "U5") (pin "32") (pinfunction "IO39_32") (pintype "unspecified+no_connect"))
    )
    (net (code "71") (name "unconnected-(U5-IO42-Pad35)") (class "Default")
      (node (ref "U5") (pin "35") (pinfunction "IO42_35") (pintype "unspecified+no_connect"))
    )
    (net (code "72") (name "unconnected-(U5-IO45-Pad26)") (class "Default")
      (node (ref "U5") (pin "26") (pinfunction "IO45_26") (pintype "unspecified+no_connect"))
    )
    (net (code "73") (name "unconnected-(U5-IO46-Pad16)") (class "Default")
      (node (ref "U5") (pin "16") (pinfunction "IO46_16") (pintype "unspecified+no_connect"))
    )
    (net (code "74") (name "unconnected-(U5-IO47-Pad24)") (class "Default")
      (node (ref "U5") (pin "24") (pinfunction "IO47_24") (pintype "unspecified+no_connect"))
    )
    (net (code "75") (name "unconnected-(U5-IO48-Pad25)") (class "Default")
      (node (ref "U5") (pin "25") (pinfunction "IO48_25") (pintype "unspecified+no_connect"))
    )
    (net (code "76") (name "unconnected-(USB1-SBU1-Pad9)") (class "Default")
      (node (ref "USB1") (pin "9") (pinfunction "SBU1_9") (pintype "unspecified+no_connect"))
    )
    (net (code "77") (name "unconnected-(USB1-SBU2-Pad3)") (class "Default")
      (node (ref "USB1") (pin "3") (pinfunction "SBU2_3") (pintype "unspecified+no_connect"))
    )
  )
)
